# Camera_connector.net
KiCad netlist of a schematic drawn in Altium Designer
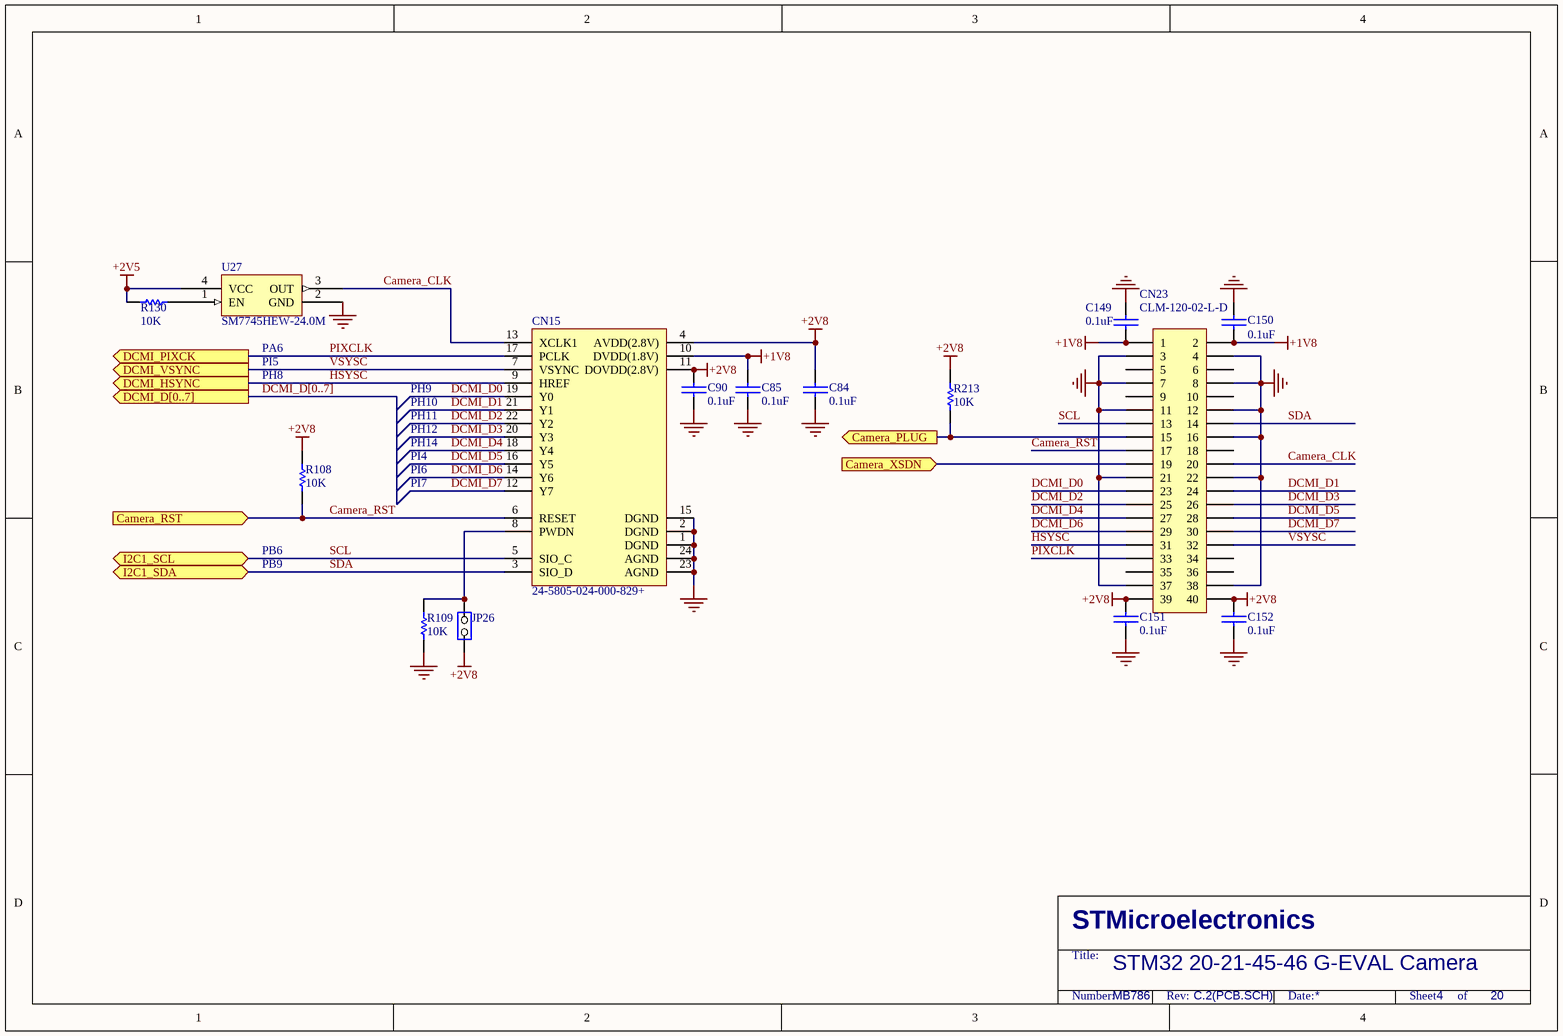
[diagram p0: Camera connector.SchDoc]

(export (version "E")
  (design (tool "Eeschema 10.0.6"))
  (components
    (comp (ref "C84")
      (value "0.1uF")
      (footprint "0402C")
      (description "Capacitor")
      (libsource (lib "*") (part "CAP"))
    )
    (comp (ref "C85")
      (value "0.1uF")
      (footprint "0402C")
      (description "Capacitor")
      (libsource (lib "*") (part "CAP"))
    )
    (comp (ref "C90")
      (value "0.1uF")
      (footprint "0402C")
      (description "Capacitor")
      (libsource (lib "*") (part "CAP"))
    )
    (comp (ref "C149")
      (value "0.1uF")
      (footprint "0402C")
      (description "Capacitor")
      (libsource (lib "*") (part "CAP"))
    )
    (comp (ref "C150")
      (value "0.1uF")
      (footprint "0402C")
      (description "Capacitor")
      (libsource (lib "*") (part "CAP"))
    )
    (comp (ref "C151")
      (value "0.1uF")
      (footprint "0402C")
      (description "Capacitor")
      (libsource (lib "*") (part "CAP"))
    )
    (comp (ref "C152")
      (value "0.1uF")
      (footprint "0402C")
      (description "Capacitor")
      (libsource (lib "*") (part "CAP"))
    )
    (comp (ref "CN15")
      (value "24-5805-024-000-829+")
      (footprint "24-5805-024-000-829")
      (libsource (lib "MB786") (part "24-5805-024-000-829+"))
    )
    (comp (ref "CN23")
      (value "CLM-120-02-L-D")
      (footprint "CLM-120-02-L-D")
      (description "Header, 20-Pin, Dual row")
      (fields (field (name "PUBLISHER") "Altium Limited"))
      (libsource (lib "Miscellaneous Connectors") (part "Header 20X2"))
    )
    (comp (ref "JP26") (value "~") (footprint "SIP2") (libsource (lib "*") (part "JP2")))
    (comp (ref "R108")
      (value "10K")
      (footprint "0402R")
      (description "Resistor")
      (fields (field (name "PUBLISHER") "Altium Limited"))
      (libsource (lib "Miscellaneous Devices") (part "Res1"))
    )
    (comp (ref "R109")
      (value "10K")
      (footprint "0402R")
      (description "Resistor")
      (fields (field (name "PUBLISHER") "Altium Limited"))
      (libsource (lib "Miscellaneous Devices") (part "Res1"))
    )
    (comp (ref "R130")
      (value "10K")
      (footprint "0402R")
      (description "Resistor")
      (fields (field (name "PUBLISHER") "Altium Limited"))
      (libsource (lib "Miscellaneous Devices") (part "Res1"))
    )
    (comp (ref "R213")
      (value "10K")
      (footprint "0402R")
      (description "Resistor")
      (fields (field (name "PUBLISHER") "Altium Limited"))
      (libsource (lib "Miscellaneous Devices") (part "Res1"))
    )
    (comp (ref "U27")
      (value "SM7745HEW-24.0M")
      (footprint "XTAL_5X7")
      (libsource (lib "MB784") (part "SM7745HEV-50.0M"))
    )
  )
  (nets
    (net (code "1") (name "+1V8") (class "Default")
      (node (ref "C149") (pin "2") (pinfunction "2_2") (pintype "passive"))
      (node (ref "C150") (pin "2") (pinfunction "2_2") (pintype "passive"))
      (node (ref "C85") (pin "2") (pinfunction "2_2") (pintype "passive"))
      (node (ref "CN15") (pin "10") (pinfunction "DVDD(1.8V)_10") (pintype "passive"))
      (node (ref "CN23") (pin "1") (pinfunction "1_1") (pintype "passive"))
      (node (ref "CN23") (pin "2") (pinfunction "2_2") (pintype "passive"))
    )
    (net (code "2") (name "+2V5") (class "Default")
      (node (ref "R130") (pin "1") (pinfunction "1_1") (pintype "passive"))
      (node (ref "U27") (pin "4") (pinfunction "VCC_4") (pintype "passive"))
    )
    (net (code "3") (name "+2V8") (class "Default")
      (node (ref "C151") (pin "2") (pinfunction "2_2") (pintype "passive"))
      (node (ref "C152") (pin "2") (pinfunction "2_2") (pintype "passive"))
      (node (ref "C84") (pin "2") (pinfunction "2_2") (pintype "passive"))
      (node (ref "C90") (pin "2") (pinfunction "2_2") (pintype "passive"))
      (node (ref "CN15") (pin "11") (pinfunction "DOVDD(2.8V)_11") (pintype "passive"))
      (node (ref "CN15") (pin "4") (pinfunction "AVDD(2.8V)_4") (pintype "passive"))
      (node (ref "CN23") (pin "39") (pinfunction "39_39") (pintype "passive"))
      (node (ref "CN23") (pin "40") (pinfunction "40_40") (pintype "passive"))
      (node (ref "JP26") (pin "1") (pinfunction "COMMON_1") (pintype "passive"))
      (node (ref "R108") (pin "2") (pinfunction "2_2") (pintype "passive"))
      (node (ref "R213") (pin "2") (pinfunction "2_2") (pintype "passive"))
    )
    (net (code "4") (name "/Camera_CLK") (class "Default")
      (node (ref "CN15") (pin "13") (pinfunction "XCLK1_13") (pintype "passive"))
      (node (ref "CN23") (pin "20") (pinfunction "20_20") (pintype "passive"))
      (node (ref "U27") (pin "3") (pinfunction "OUT_3") (pintype "output"))
    )
    (net (code "5") (name "/Camera_PLUG") (class "Default")
      (node (ref "CN23") (pin "15") (pinfunction "15_15") (pintype "passive"))
      (node (ref "R213") (pin "1") (pinfunction "1_1") (pintype "passive"))
    )
    (net (code "6") (name "/Camera_RST") (class "Default")
      (node (ref "CN15") (pin "6") (pinfunction "RESET_6") (pintype "passive"))
      (node (ref "CN23") (pin "17") (pinfunction "17_17") (pintype "passive"))
      (node (ref "R108") (pin "1") (pinfunction "1_1") (pintype "passive"))
    )
    (net (code "7") (name "/Camera_XSDN") (class "Default")
      (node (ref "CN23") (pin "19") (pinfunction "19_19") (pintype "passive"))
    )
    (net (code "8") (name "/DCMI_D0") (class "Default")
      (node (ref "CN15") (pin "19") (pinfunction "Y0_19") (pintype "passive"))
      (node (ref "CN23") (pin "23") (pinfunction "23_23") (pintype "passive"))
    )
    (net (code "9") (name "/DCMI_D1") (class "Default")
      (node (ref "CN15") (pin "21") (pinfunction "Y1_21") (pintype "passive"))
      (node (ref "CN23") (pin "24") (pinfunction "24_24") (pintype "passive"))
    )
    (net (code "10") (name "/DCMI_D2") (class "Default")
      (node (ref "CN15") (pin "22") (pinfunction "Y2_22") (pintype "passive"))
      (node (ref "CN23") (pin "25") (pinfunction "25_25") (pintype "passive"))
    )
    (net (code "11") (name "/DCMI_D3") (class "Default")
      (node (ref "CN15") (pin "20") (pinfunction "Y3_20") (pintype "passive"))
      (node (ref "CN23") (pin "26") (pinfunction "26_26") (pintype "passive"))
    )
    (net (code "12") (name "/DCMI_D4") (class "Default")
      (node (ref "CN15") (pin "18") (pinfunction "Y4_18") (pintype "passive"))
      (node (ref "CN23") (pin "27") (pinfunction "27_27") (pintype "passive"))
    )
    (net (code "13") (name "/DCMI_D5") (class "Default")
      (node (ref "CN15") (pin "16") (pinfunction "Y5_16") (pintype "passive"))
      (node (ref "CN23") (pin "28") (pinfunction "28_28") (pintype "passive"))
    )
    (net (code "14") (name "/DCMI_D6") (class "Default")
      (node (ref "CN15") (pin "14") (pinfunction "Y6_14") (pintype "passive"))
      (node (ref "CN23") (pin "29") (pinfunction "29_29") (pintype "passive"))
    )
    (net (code "15") (name "/DCMI_D7") (class "Default")
      (node (ref "CN15") (pin "12") (pinfunction "Y7_12") (pintype "passive"))
      (node (ref "CN23") (pin "30") (pinfunction "30_30") (pintype "passive"))
    )
    (net (code "17") (name "/HSYSC") (class "Default")
      (node (ref "CN15") (pin "9") (pinfunction "HREF_9") (pintype "passive"))
      (node (ref "CN23") (pin "31") (pinfunction "31_31") (pintype "passive"))
    )
    (net (code "18") (name "/PIXCLK") (class "Default")
      (node (ref "CN15") (pin "17") (pinfunction "PCLK_17") (pintype "passive"))
      (node (ref "CN23") (pin "33") (pinfunction "33_33") (pintype "passive"))
    )
    (net (code "19") (name "/SCL") (class "Default")
      (node (ref "CN15") (pin "5") (pinfunction "SIO_C_5") (pintype "passive"))
      (node (ref "CN23") (pin "13") (pinfunction "13_13") (pintype "passive"))
    )
    (net (code "20") (name "/SDA") (class "Default")
      (node (ref "CN15") (pin "3") (pinfunction "SIO_D_3") (pintype "passive"))
      (node (ref "CN23") (pin "14") (pinfunction "14_14") (pintype "passive"))
    )
    (net (code "21") (name "/VSYSC") (class "Default")
      (node (ref "CN15") (pin "7") (pinfunction "VSYNC_7") (pintype "passive"))
      (node (ref "CN23") (pin "32") (pinfunction "32_32") (pintype "passive"))
    )
    (net (code "22") (name "GND") (class "Default")
      (node (ref "C149") (pin "1") (pinfunction "1_1") (pintype "passive"))
      (node (ref "C150") (pin "1") (pinfunction "1_1") (pintype "passive"))
      (node (ref "C151") (pin "1") (pinfunction "1_1") (pintype "passive"))
      (node (ref "C152") (pin "1") (pinfunction "1_1") (pintype "passive"))
      (node (ref "C84") (pin "1") (pinfunction "1_1") (pintype "passive"))
      (node (ref "C85") (pin "1") (pinfunction "1_1") (pintype "passive"))
      (node (ref "C90") (pin "1") (pinfunction "1_1") (pintype "passive"))
      (node (ref "CN15") (pin "1") (pinfunction "DGND_1") (pintype "passive"))
      (node (ref "CN15") (pin "15") (pinfunction "DGND_15") (pintype "passive"))
      (node (ref "CN15") (pin "2") (pinfunction "DGND_2") (pintype "passive"))
      (node (ref "CN15") (pin "23") (pinfunction "AGND_23") (pintype "passive"))
      (node (ref "CN15") (pin "24") (pinfunction "AGND_24") (pintype "passive"))
      (node (ref "CN23") (pin "11") (pinfunction "11_11") (pintype "passive"))
      (node (ref "CN23") (pin "12") (pinfunction "12_12") (pintype "passive"))
      (node (ref "CN23") (pin "16") (pinfunction "16_16") (pintype "passive"))
      (node (ref "CN23") (pin "21") (pinfunction "21_21") (pintype "passive"))
      (node (ref "CN23") (pin "22") (pinfunction "22_22") (pintype "passive"))
      (node (ref "CN23") (pin "3") (pinfunction "3_3") (pintype "passive"))
      (node (ref "CN23") (pin "37") (pinfunction "37_37") (pintype "passive"))
      (node (ref "CN23") (pin "38") (pinfunction "38_38") (pintype "passive"))
      (node (ref "CN23") (pin "4") (pinfunction "4_4") (pintype "passive"))
      (node (ref "CN23") (pin "7") (pinfunction "7_7") (pintype "passive"))
      (node (ref "CN23") (pin "8") (pinfunction "8_8") (pintype "passive"))
      (node (ref "R109") (pin "1") (pinfunction "1_1") (pintype "passive"))
      (node (ref "U27") (pin "2") (pinfunction "GND_2") (pintype "passive"))
    )
    (net (code "23") (name "Net-(CN15-PWDN)") (class "Default")
      (node (ref "CN15") (pin "8") (pinfunction "PWDN_8") (pintype "passive"))
      (node (ref "JP26") (pin "2") (pinfunction "NO_2") (pintype "passive"))
      (node (ref "R109") (pin "2") (pinfunction "2_2") (pintype "passive"))
    )
    (net (code "24") (name "Net-(U27-EN)") (class "Default")
      (node (ref "R130") (pin "2") (pinfunction "2_2") (pintype "passive"))
      (node (ref "U27") (pin "1") (pinfunction "EN_1") (pintype "input"))
    )
    (net (code "25") (name "unconnected-(CN23-Pad5)") (class "Default")
      (node (ref "CN23") (pin "5") (pinfunction "5_5") (pintype "passive"))
    )
    (net (code "26") (name "unconnected-(CN23-Pad6)") (class "Default")
      (node (ref "CN23") (pin "6") (pinfunction "6_6") (pintype "passive"))
    )
    (net (code "27") (name "unconnected-(CN23-Pad9)") (class "Default")
      (node (ref "CN23") (pin "9") (pinfunction "9_9") (pintype "passive"))
    )
    (net (code "28") (name "unconnected-(CN23-Pad10)") (class "Default")
      (node (ref "CN23") (pin "10") (pinfunction "10_10") (pintype "passive"))
    )
    (net (code "29") (name "unconnected-(CN23-Pad18)") (class "Default")
      (node (ref "CN23") (pin "18") (pinfunction "18_18") (pintype "passive"))
    )
    (net (code "30") (name "unconnected-(CN23-Pad34)") (class "Default")
      (node (ref "CN23") (pin "34") (pinfunction "34_34") (pintype "passive"))
    )
    (net (code "31") (name "unconnected-(CN23-Pad35)") (class "Default")
      (node (ref "CN23") (pin "35") (pinfunction "35_35") (pintype "passive"))
    )
    (net (code "32") (name "unconnected-(CN23-Pad36)") (class "Default")
      (node (ref "CN23") (pin "36") (pinfunction "36_36") (pintype "passive"))
    )
  )
)
